# SCH_2_Battery_Power_Management.net
KiCad netlist of a schematic drawn in Altium Designer
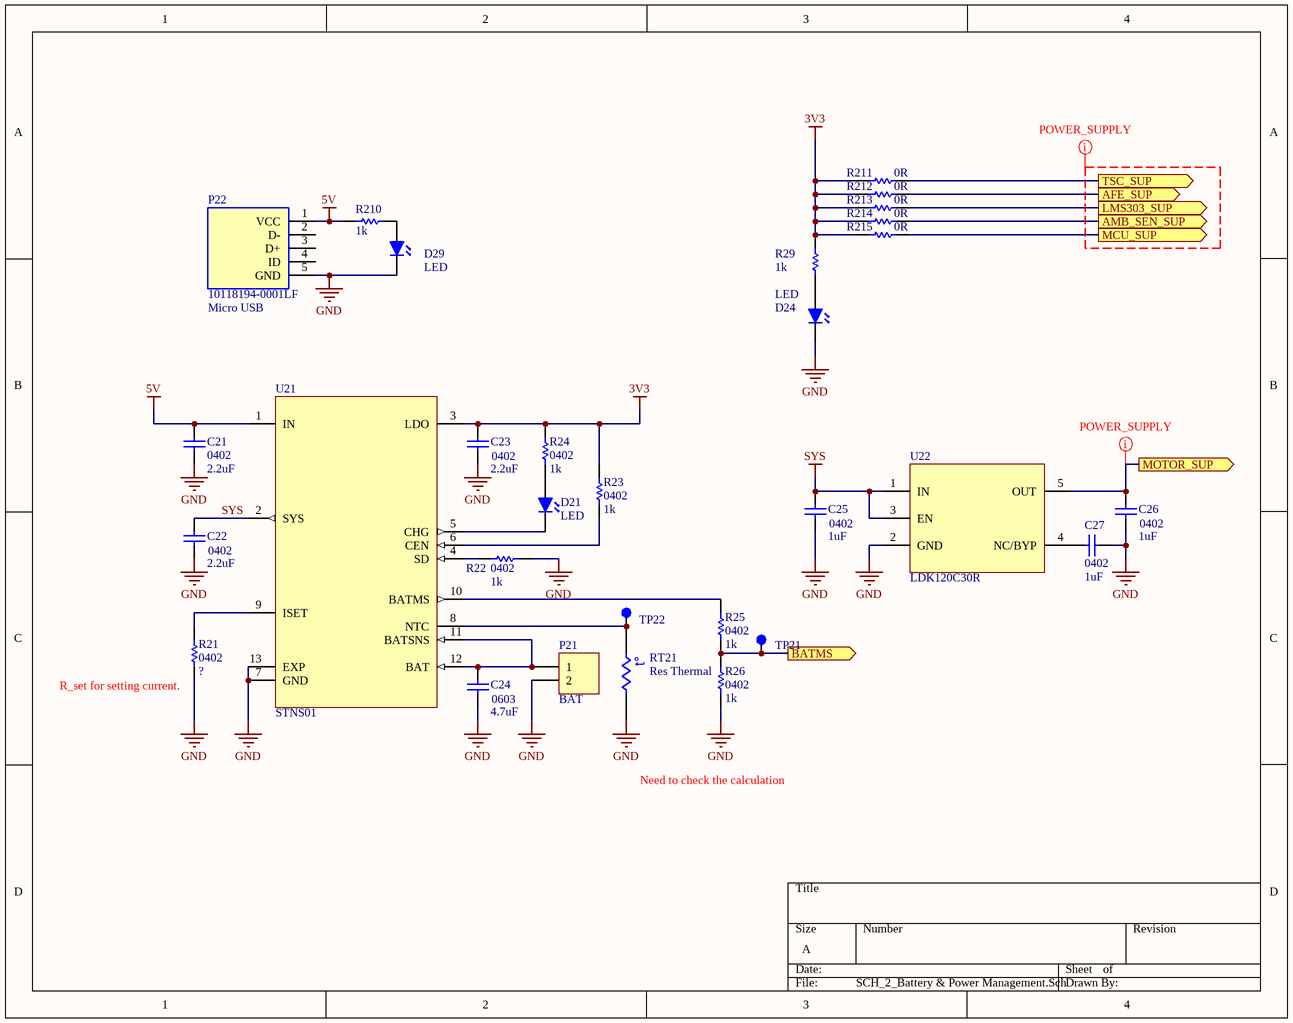
[diagram p0: SCH_2_Battery & Power Management.SchDoc]

(export (version "E")
  (design (tool "Eeschema 10.0.6"))
  (components
    (comp (ref "C21")
      (value "0402")
      (footprint "CAPC1005X07N")
      (description "Capacitor")
      (fields (field (name "ALTIUM_VALUE") "2.2uF") (field (name "PUBLISHER") "Altium Limited"))
      (libsource (lib "Miscellaneous Devices") (part "Cap"))
    )
    (comp (ref "C22")
      (value "0402")
      (footprint "CAPC1005X07N")
      (description "Capacitor")
      (fields (field (name "ALTIUM_VALUE") "2.2uF") (field (name "PUBLISHER") "Altium Limited"))
      (libsource (lib "Miscellaneous Devices") (part "Cap"))
    )
    (comp (ref "C23")
      (value "0402")
      (footprint "CAPC1005X07N")
      (description "Capacitor")
      (fields (field (name "ALTIUM_VALUE") "2.2uF") (field (name "PUBLISHER") "Altium Limited"))
      (libsource (lib "Miscellaneous Devices") (part "Cap"))
    )
    (comp (ref "C24")
      (value "0603")
      (footprint "CAPC1608X10N")
      (description "Capacitor")
      (fields (field (name "ALTIUM_VALUE") "4.7uF") (field (name "PUBLISHER") "Altium Limited"))
      (libsource (lib "Miscellaneous Devices") (part "Cap"))
    )
    (comp (ref "C25")
      (value "0402")
      (footprint "CAPC1005X07N")
      (description "Capacitor")
      (fields (field (name "ALTIUM_VALUE") "1uF") (field (name "PUBLISHER") "Altium Limited"))
      (libsource (lib "Miscellaneous Devices") (part "Cap"))
    )
    (comp (ref "C26")
      (value "0402")
      (footprint "CAPC1005X07N")
      (description "Capacitor")
      (fields (field (name "ALTIUM_VALUE") "1uF") (field (name "PUBLISHER") "Altium Limited"))
      (libsource (lib "Miscellaneous Devices") (part "Cap"))
    )
    (comp (ref "C27")
      (value "0402")
      (footprint "CAPC1005X07N")
      (description "Capacitor")
      (fields (field (name "ALTIUM_VALUE") "1uF") (field (name "PUBLISHER") "Altium Limited"))
      (libsource (lib "Miscellaneous Devices") (part "Cap"))
    )
    (comp (ref "D21")
      (value "LED")
      (footprint "LED_1005X05N")
      (description "General LED")
      (libsource (lib "Schematic_IC_Diode") (part "LED"))
    )
    (comp (ref "D24")
      (value "LED")
      (footprint "LED_1005X05N")
      (description "General LED")
      (libsource (lib "Schematic_IC_Diode") (part "LED"))
    )
    (comp (ref "D29")
      (value "LED")
      (footprint "LED_1005X05N")
      (description "General LED")
      (libsource (lib "Schematic_IC_Diode") (part "LED"))
    )
    (comp (ref "P21")
      (value "BAT")
      (footprint "HDR1X2")
      (description "Li-Poly Battery")
      (fields (field (name "PUBLISHER") "Altium Limited"))
      (libsource (lib "Miscellaneous Connectors") (part "MHDR1X2"))
    )
    (comp (ref "P22")
      (value "Micro USB")
      (footprint "USB_Mirco_Amphenol FCI_10118194")
      (description "General  Micro USB")
      (fields (field (name "MANUFACTURE P/N") "10118194-0001LF"))
      (libsource (lib "Schematic_Connectors_USB") (part "CONN_MICRO_USB"))
    )
    (comp (ref "R21")
      (value "0402")
      (footprint "RESC1005X04N")
      (description "Resistor")
      (fields (field (name "ALTIUM_VALUE") "?") (field (name "PUBLISHER") "Altium Limited"))
      (libsource (lib "Miscellaneous Devices") (part "Res1"))
    )
    (comp (ref "R22")
      (value "0402")
      (footprint "RESC1005X04N")
      (description "Resistor")
      (fields (field (name "ALTIUM_VALUE") "1k") (field (name "PUBLISHER") "Altium Limited"))
      (libsource (lib "Miscellaneous Devices") (part "Res1"))
    )
    (comp (ref "R23")
      (value "0402")
      (footprint "RESC1005X04N")
      (description "Resistor")
      (fields (field (name "ALTIUM_VALUE") "1k") (field (name "PUBLISHER") "Altium Limited"))
      (libsource (lib "Miscellaneous Devices") (part "Res1"))
    )
    (comp (ref "R24")
      (value "0402")
      (footprint "RESC1005X04N")
      (description "Resistor")
      (fields (field (name "ALTIUM_VALUE") "1k") (field (name "PUBLISHER") "Altium Limited"))
      (libsource (lib "Miscellaneous Devices") (part "Res1"))
    )
    (comp (ref "R25")
      (value "0402")
      (footprint "RESC1005X04N")
      (description "Resistor")
      (fields (field (name "ALTIUM_VALUE") "1k") (field (name "PUBLISHER") "Altium Limited"))
      (libsource (lib "Miscellaneous Devices") (part "Res1"))
    )
    (comp (ref "R26")
      (value "0402")
      (footprint "RESC1005X04N")
      (description "Resistor")
      (fields (field (name "ALTIUM_VALUE") "1k") (field (name "PUBLISHER") "Altium Limited"))
      (libsource (lib "Miscellaneous Devices") (part "Res1"))
    )
    (comp (ref "R29")
      (value "1k")
      (footprint "RESC1005X04N")
      (description "Resistor")
      (fields (field (name "Comment") "0402") (field (name "PUBLISHER") "Altium Limited"))
      (libsource (lib "Miscellaneous Devices") (part "Res1"))
    )
    (comp (ref "R210")
      (value "1k")
      (footprint "RESC1005X04N")
      (description "Resistor")
      (fields (field (name "Comment") "0402") (field (name "PUBLISHER") "Altium Limited"))
      (libsource (lib "Miscellaneous Devices") (part "Res1"))
    )
    (comp (ref "R211")
      (value "0R")
      (footprint "RESC1005X04N")
      (description "Resistor")
      (fields (field (name "Comment") "0402") (field (name "PUBLISHER") "Altium Limited"))
      (libsource (lib "Miscellaneous Devices") (part "Res1"))
    )
    (comp (ref "R212")
      (value "0R")
      (footprint "RESC1005X04N")
      (description "Resistor")
      (fields (field (name "Comment") "0402") (field (name "PUBLISHER") "Altium Limited"))
      (libsource (lib "Miscellaneous Devices") (part "Res1"))
    )
    (comp (ref "R213")
      (value "0R")
      (footprint "RESC1005X04N")
      (description "Resistor")
      (fields (field (name "Comment") "0402") (field (name "PUBLISHER") "Altium Limited"))
      (libsource (lib "Miscellaneous Devices") (part "Res1"))
    )
    (comp (ref "R214")
      (value "0R")
      (footprint "RESC1005X04N")
      (description "Resistor")
      (fields (field (name "Comment") "0402") (field (name "PUBLISHER") "Altium Limited"))
      (libsource (lib "Miscellaneous Devices") (part "Res1"))
    )
    (comp (ref "R215")
      (value "0R")
      (footprint "RESC1005X04N")
      (description "Resistor")
      (fields (field (name "Comment") "0402") (field (name "PUBLISHER") "Altium Limited"))
      (libsource (lib "Miscellaneous Devices") (part "Res1"))
    )
    (comp (ref "RT21")
      (value "Res Thermal")
      (footprint "MHDR1X2")
      (description "Thermistor")
      (fields (field (name "PUBLISHER") "Altium Limited"))
      (libsource (lib "Miscellaneous Devices") (part "Res Thermal"))
    )
    (comp (ref "TP21")
      (value "TP")
      (footprint "TP100")
      (description "Test Point dot type")
      (libsource (lib "Schematic_Test_Points") (part "TP_A"))
    )
    (comp (ref "TP22")
      (value "TP")
      (footprint "TP100")
      (description "Test Point dot type")
      (libsource (lib "Schematic_Test_Points") (part "TP_A"))
    )
    (comp (ref "U21")
      (value "STNS01")
      (footprint "DFN45P300X300X80-12N_HS200X120")
      (description "Battery Charger Li-Ion 200mA with LDO 100mA 12-Pin DFN EP T/R")
      (libsource (lib "Schematic_IC_Power_Management") (part "STNS01"))
    )
    (comp (ref "U22")
      (value "LDK120C30R")
      (footprint "SOT65P210X110-5L")
      (description "IC REG LDO 3V 0.2A SOT323-5")
      (fields (field (name "MANUFACTURER") "STMicroelectronics") (field (name "TOLERANCE") "2%"))
      (libsource (lib "Schematic_IC_Power_Management") (part "LDK120C30R"))
    )
  )
  (nets
    (net (code "1") (name "/AFE_SUP") (class "Default")
      (node (ref "R212") (pin "2") (pinfunction "2_2") (pintype "passive"))
    )
    (net (code "2") (name "/AMB_SEN_SUP") (class "Default")
      (node (ref "R214") (pin "2") (pinfunction "2_2") (pintype "passive"))
    )
    (net (code "3") (name "/BATMS") (class "Default")
      (node (ref "R25") (pin "2") (pinfunction "2_2") (pintype "passive"))
      (node (ref "R26") (pin "1") (pinfunction "1_1") (pintype "passive"))
      (node (ref "TP21") (pin "1") (pintype "passive"))
    )
    (net (code "4") (name "/LMS303_SUP") (class "Default")
      (node (ref "R213") (pin "2") (pinfunction "2_2") (pintype "passive"))
    )
    (net (code "5") (name "/MCU_SUP") (class "Default")
      (node (ref "R215") (pin "2") (pinfunction "2_2") (pintype "passive"))
    )
    (net (code "6") (name "/MOTOR_SUP") (class "Default")
      (node (ref "C26") (pin "2") (pinfunction "2_2") (pintype "passive"))
      (node (ref "U22") (pin "5") (pinfunction "OUT_5") (pintype "passive"))
    )
    (net (code "7") (name "/TSC_SUP") (class "Default")
      (node (ref "R211") (pin "2") (pinfunction "2_2") (pintype "passive"))
    )
    (net (code "8") (name "3V3") (class "Default")
      (node (ref "C23") (pin "2") (pinfunction "2_2") (pintype "passive"))
      (node (ref "R211") (pin "1") (pinfunction "1_1") (pintype "passive"))
      (node (ref "R212") (pin "1") (pinfunction "1_1") (pintype "passive"))
      (node (ref "R213") (pin "1") (pinfunction "1_1") (pintype "passive"))
      (node (ref "R214") (pin "1") (pinfunction "1_1") (pintype "passive"))
      (node (ref "R215") (pin "1") (pinfunction "1_1") (pintype "passive"))
      (node (ref "R23") (pin "1") (pinfunction "1_1") (pintype "passive"))
      (node (ref "R24") (pin "1") (pinfunction "1_1") (pintype "passive"))
      (node (ref "R29") (pin "1") (pinfunction "1_1") (pintype "passive"))
      (node (ref "U21") (pin "3") (pinfunction "LDO_3") (pintype "power_in"))
    )
    (net (code "9") (name "5V") (class "Default")
      (node (ref "C21") (pin "2") (pinfunction "2_2") (pintype "passive"))
      (node (ref "P22") (pin "1") (pinfunction "VCC_1") (pintype "passive"))
      (node (ref "R210") (pin "1") (pinfunction "1_1") (pintype "passive"))
      (node (ref "U21") (pin "1") (pinfunction "IN_1") (pintype "power_in"))
    )
    (net (code "10") (name "GND") (class "Default")
      (node (ref "C21") (pin "1") (pinfunction "1_1") (pintype "passive"))
      (node (ref "C22") (pin "1") (pinfunction "1_1") (pintype "passive"))
      (node (ref "C23") (pin "1") (pinfunction "1_1") (pintype "passive"))
      (node (ref "C24") (pin "1") (pinfunction "1_1") (pintype "passive"))
      (node (ref "C25") (pin "1") (pinfunction "1_1") (pintype "passive"))
      (node (ref "C26") (pin "1") (pinfunction "1_1") (pintype "passive"))
      (node (ref "C27") (pin "1") (pinfunction "1_1") (pintype "passive"))
      (node (ref "D24") (pin "2") (pinfunction "-_2") (pintype "passive"))
      (node (ref "D29") (pin "2") (pinfunction "-_2") (pintype "passive"))
      (node (ref "P21") (pin "2") (pinfunction "2_2") (pintype "passive"))
      (node (ref "P22") (pin "5") (pinfunction "GND_5") (pintype "passive"))
      (node (ref "R21") (pin "1") (pinfunction "1_1") (pintype "passive"))
      (node (ref "R22") (pin "1") (pinfunction "1_1") (pintype "passive"))
      (node (ref "R26") (pin "2") (pinfunction "2_2") (pintype "passive"))
      (node (ref "RT21") (pin "2") (pinfunction "2_2") (pintype "passive"))
      (node (ref "U21") (pin "13") (pinfunction "EXP_13") (pintype "passive"))
      (node (ref "U21") (pin "7") (pinfunction "GND_7") (pintype "power_in"))
      (node (ref "U22") (pin "2") (pinfunction "GND_2") (pintype "passive"))
    )
    (net (code "11") (name "Net-(D21-+)") (class "Default")
      (node (ref "D21") (pin "1") (pinfunction "+_1") (pintype "passive"))
      (node (ref "R24") (pin "2") (pinfunction "2_2") (pintype "passive"))
    )
    (net (code "12") (name "Net-(D21--)") (class "Default")
      (node (ref "D21") (pin "2") (pinfunction "-_2") (pintype "passive"))
      (node (ref "U21") (pin "5") (pinfunction "CHG_5") (pintype "output"))
    )
    (net (code "13") (name "Net-(D24-+)") (class "Default")
      (node (ref "D24") (pin "1") (pinfunction "+_1") (pintype "passive"))
      (node (ref "R29") (pin "2") (pinfunction "2_2") (pintype "passive"))
    )
    (net (code "14") (name "Net-(D29-+)") (class "Default")
      (node (ref "D29") (pin "1") (pinfunction "+_1") (pintype "passive"))
      (node (ref "R210") (pin "2") (pinfunction "2_2") (pintype "passive"))
    )
    (net (code "15") (name "Net-(U21-BAT)") (class "Default")
      (node (ref "C24") (pin "2") (pinfunction "2_2") (pintype "passive"))
      (node (ref "P21") (pin "1") (pinfunction "1_1") (pintype "passive"))
      (node (ref "U21") (pin "11") (pinfunction "BATSNS_11") (pintype "input"))
      (node (ref "U21") (pin "12") (pinfunction "BAT_12") (pintype "input"))
    )
    (net (code "16") (name "Net-(U21-BATMS)") (class "Default")
      (node (ref "R25") (pin "1") (pinfunction "1_1") (pintype "passive"))
      (node (ref "U21") (pin "10") (pinfunction "BATMS_10") (pintype "output"))
    )
    (net (code "17") (name "Net-(U21-CEN)") (class "Default")
      (node (ref "R23") (pin "2") (pinfunction "2_2") (pintype "passive"))
      (node (ref "U21") (pin "6") (pinfunction "CEN_6") (pintype "input"))
    )
    (net (code "18") (name "Net-(U21-ISET)") (class "Default")
      (node (ref "R21") (pin "2") (pinfunction "2_2") (pintype "passive"))
      (node (ref "U21") (pin "9") (pinfunction "ISET_9") (pintype "passive"))
    )
    (net (code "19") (name "Net-(U21-NTC)") (class "Default")
      (node (ref "RT21") (pin "1") (pinfunction "1_1") (pintype "passive"))
      (node (ref "TP22") (pin "1") (pintype "passive"))
      (node (ref "U21") (pin "8") (pinfunction "NTC_8") (pintype "passive"))
    )
    (net (code "20") (name "Net-(U21-SD)") (class "Default")
      (node (ref "R22") (pin "2") (pinfunction "2_2") (pintype "passive"))
      (node (ref "U21") (pin "4") (pinfunction "SD_4") (pintype "input"))
    )
    (net (code "21") (name "Net-(U22-NC{slash}BYP)") (class "Default")
      (node (ref "C27") (pin "2") (pinfunction "2_2") (pintype "passive"))
      (node (ref "U22") (pin "4") (pinfunction "NC/BYP_4") (pintype "passive"))
    )
    (net (code "22") (name "SYS") (class "Default")
      (node (ref "C22") (pin "2") (pinfunction "2_2") (pintype "passive"))
      (node (ref "C25") (pin "2") (pinfunction "2_2") (pintype "passive"))
      (node (ref "U21") (pin "2") (pinfunction "SYS_2") (pintype "output"))
      (node (ref "U22") (pin "1") (pinfunction "IN_1") (pintype "passive"))
      (node (ref "U22") (pin "3") (pinfunction "EN_3") (pintype "passive"))
    )
    (net (code "23") (name "unconnected-(P22-D+-Pad3)") (class "Default")
      (node (ref "P22") (pin "3") (pinfunction "D+_3") (pintype "passive"))
    )
    (net (code "24") (name "unconnected-(P22-D--Pad2)") (class "Default")
      (node (ref "P22") (pin "2") (pinfunction "D-_2") (pintype "passive"))
    )
    (net (code "25") (name "unconnected-(P22-ID-Pad4)") (class "Default")
      (node (ref "P22") (pin "4") (pinfunction "ID_4") (pintype "passive"))
    )
  )
)
